# uduck.net
KiCad netlist of a schematic drawn in EAGLE
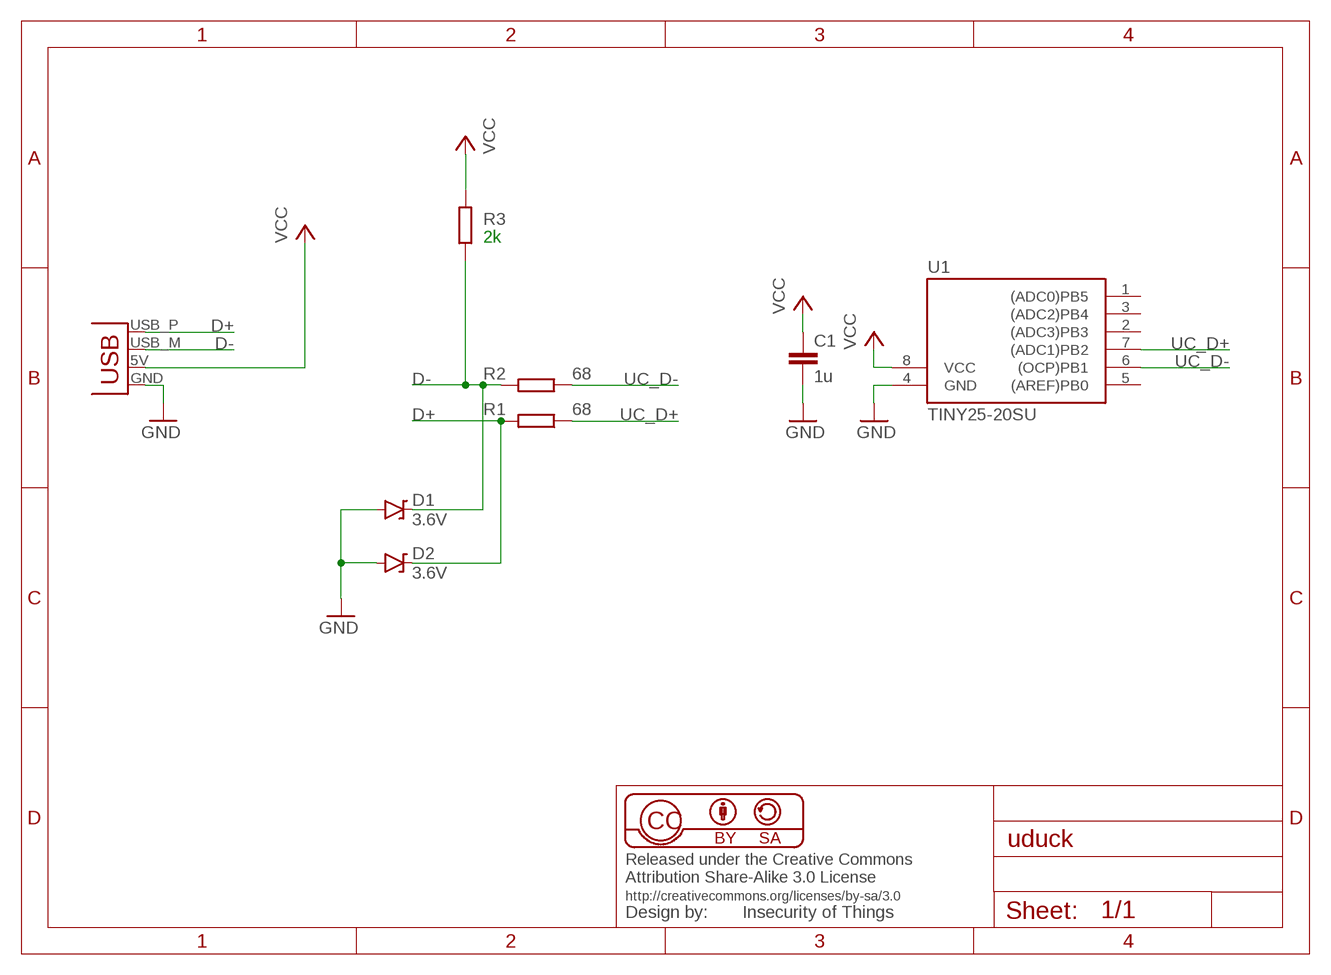
[diagram p0: schematic, sheet 1]

(export (version "E")
  (design (tool "Eeschema 10.0.6"))
  (components
    (comp (ref "C1")
      (value "1u")
      (footprint "eagle-import:C0805")
      (libsource (lib "eagle-import") (part "C-EUC0805"))
    )
    (comp (ref "D1")
      (value "3.6V")
      (footprint "eagle-import:SOD-323")
      (libsource (lib "eagle-import") (part "DIODE-ZENER3.3V"))
    )
    (comp (ref "D2")
      (value "3.6V")
      (footprint "eagle-import:SOD-323")
      (libsource (lib "eagle-import") (part "DIODE-ZENER3.3V"))
    )
    (comp (ref "R1")
      (value "68")
      (footprint "eagle-import:R0603")
      (libsource (lib "eagle-import") (part "R-EU_R0603"))
    )
    (comp (ref "R2")
      (value "68")
      (footprint "eagle-import:R0603")
      (libsource (lib "eagle-import") (part "R-EU_R0603"))
    )
    (comp (ref "R3")
      (value "2k")
      (footprint "eagle-import:R0603")
      (libsource (lib "eagle-import") (part "R-EU_R0603"))
    )
    (comp (ref "U1")
      (value "TINY25-20SU")
      (footprint "eagle-import:SOIC8")
      (libsource (lib "eagle-import") (part "TINY25-20SU"))
    )
    (comp (ref "X1")
      (value "USBPCB")
      (footprint "eagle-import:USB-A-PCB")
      (libsource (lib "eagle-import") (part "USBPCB"))
    )
  )
  (nets
    (net (code "1") (name "/D+") (class "Default")
      (node (ref "D2") (pin "C") (pinfunction "C_C") (pintype "passive"))
      (node (ref "R1") (pin "2") (pinfunction "2_2") (pintype "passive"))
      (node (ref "X1") (pin "USB_P") (pinfunction "D+_USB_P") (pintype "bidirectional"))
    )
    (net (code "2") (name "/D-") (class "Default")
      (node (ref "D1") (pin "C") (pinfunction "C_C") (pintype "passive"))
      (node (ref "R2") (pin "2") (pinfunction "2_2") (pintype "passive"))
      (node (ref "R3") (pin "1") (pinfunction "1_1") (pintype "passive"))
      (node (ref "X1") (pin "USB_M") (pinfunction "D-_USB_M") (pintype "bidirectional"))
    )
    (net (code "3") (name "/UC_D+") (class "Default")
      (node (ref "R1") (pin "1") (pinfunction "1_1") (pintype "passive"))
      (node (ref "U1") (pin "7") (pinfunction "(ADC1)PB2_7") (pintype "bidirectional"))
    )
    (net (code "4") (name "/UC_D-") (class "Default")
      (node (ref "R2") (pin "1") (pinfunction "1_1") (pintype "passive"))
      (node (ref "U1") (pin "6") (pinfunction "(OCP)PB1_6") (pintype "bidirectional"))
    )
    (net (code "5") (name "GND") (class "Default")
      (node (ref "C1") (pin "2") (pinfunction "2_2") (pintype "passive"))
      (node (ref "D1") (pin "A") (pinfunction "A_A") (pintype "passive"))
      (node (ref "D2") (pin "A") (pinfunction "A_A") (pintype "passive"))
      (node (ref "U1") (pin "4") (pinfunction "GND_4") (pintype "power_in"))
      (node (ref "X1") (pin "GND") (pinfunction "GND_GND") (pintype "bidirectional"))
    )
    (net (code "6") (name "VCC") (class "Default")
      (node (ref "C1") (pin "1") (pinfunction "1_1") (pintype "passive"))
      (node (ref "R3") (pin "2") (pinfunction "2_2") (pintype "passive"))
      (node (ref "U1") (pin "8") (pinfunction "VCC_8") (pintype "power_in"))
      (node (ref "X1") (pin "5V") (pinfunction "VBUS_5V") (pintype "bidirectional"))
    )
    (net (code "7") (name "unconnected-(U1-(ADC0)PB5-Pad1)") (class "Default")
      (node (ref "U1") (pin "1") (pinfunction "(ADC0)PB5_1") (pintype "bidirectional"))
    )
    (net (code "8") (name "unconnected-(U1-(ADC2)PB4-Pad3)") (class "Default")
      (node (ref "U1") (pin "3") (pinfunction "(ADC2)PB4_3") (pintype "bidirectional"))
    )
    (net (code "9") (name "unconnected-(U1-(ADC3)PB3-Pad2)") (class "Default")
      (node (ref "U1") (pin "2") (pinfunction "(ADC3)PB3_2") (pintype "bidirectional"))
    )
    (net (code "10") (name "unconnected-(U1-(AREF)PB0-Pad5)") (class "Default")
      (node (ref "U1") (pin "5") (pinfunction "(AREF)PB0_5") (pintype "bidirectional"))
    )
  )
)
